# T-Board-328_PCB_-_v0_3.net
KiCad netlist of a schematic drawn in EAGLE
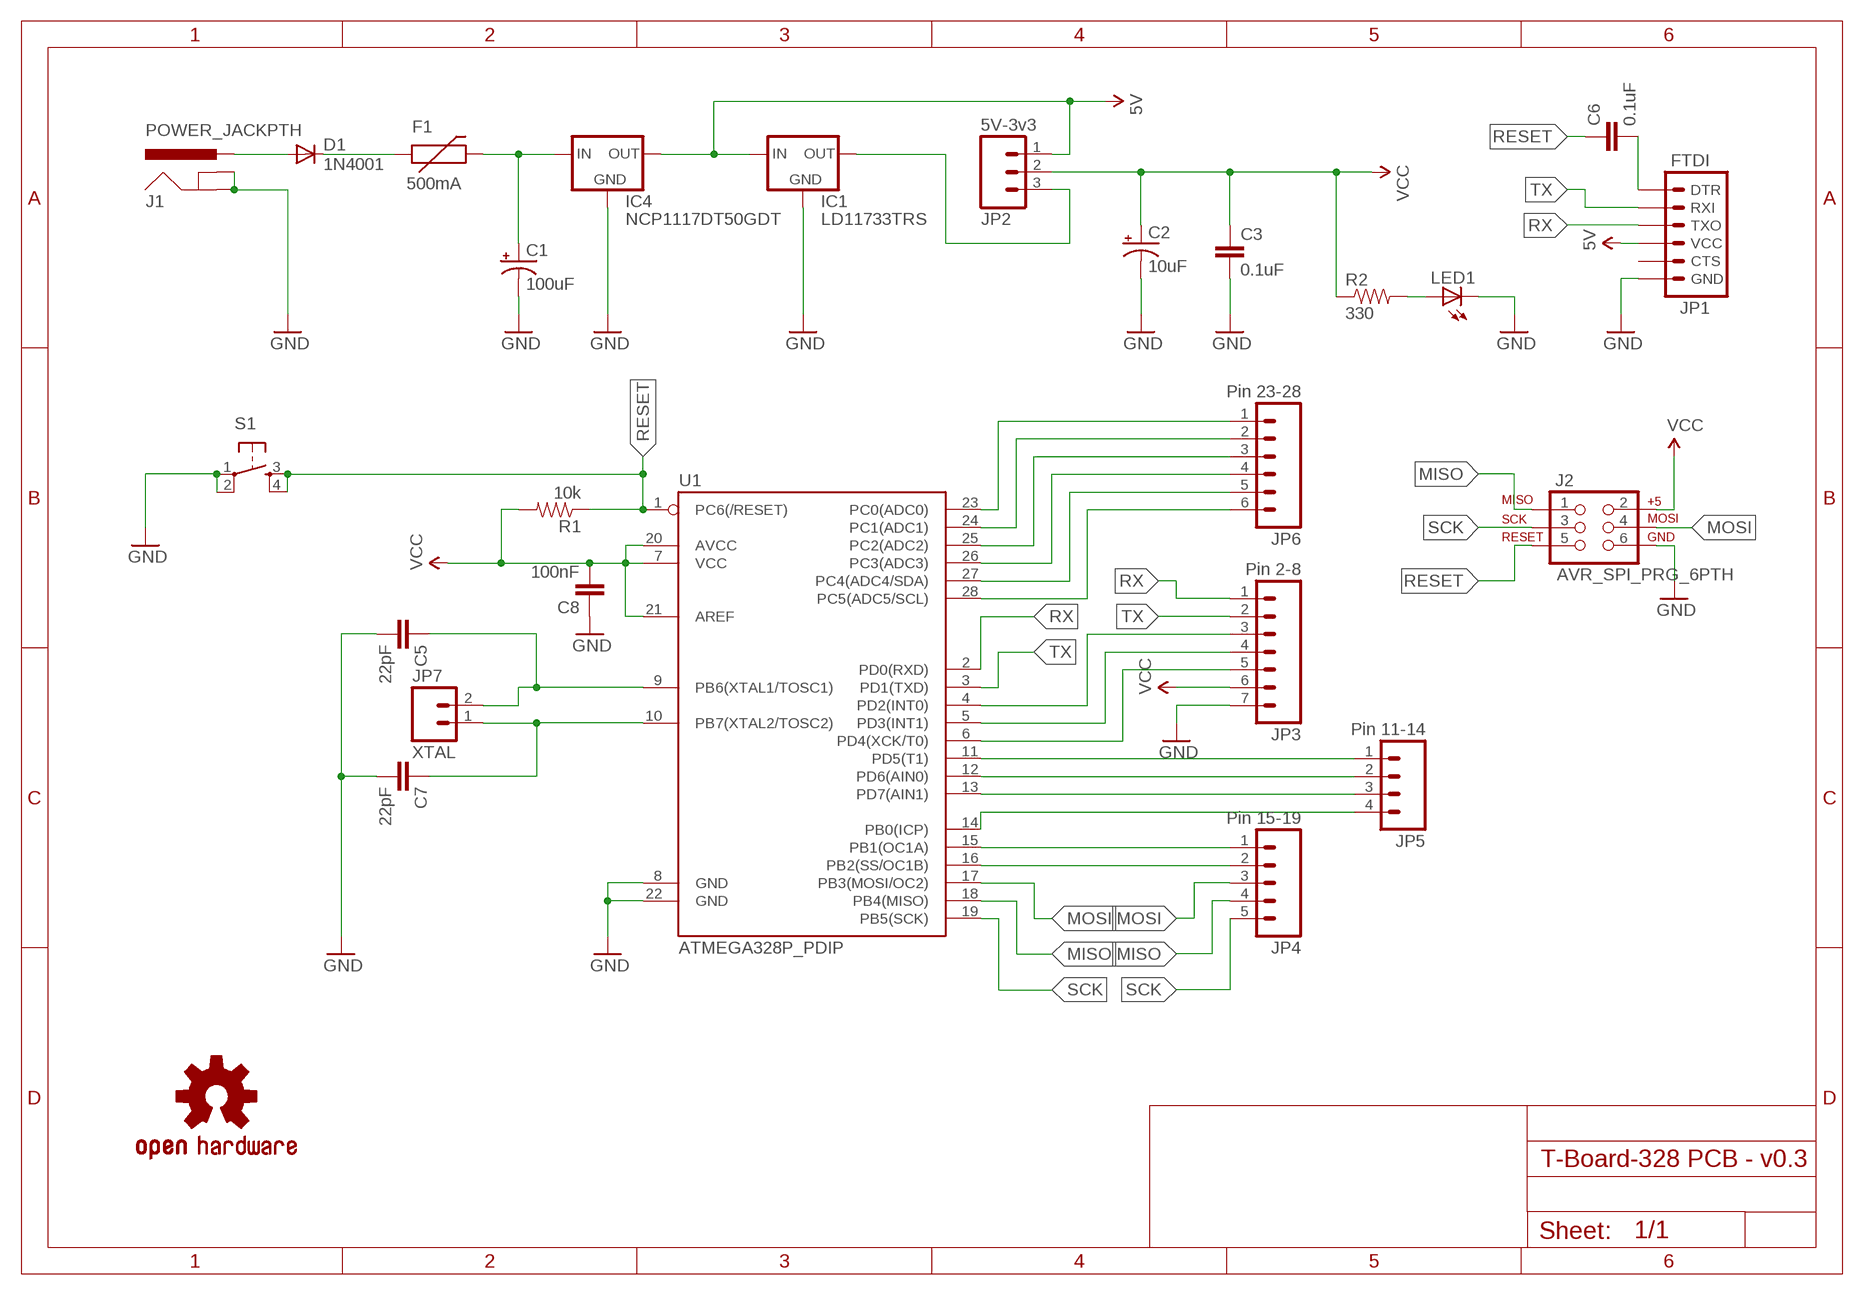
[diagram p0: schematic, sheet 1]

(export (version "E")
  (design (tool "Eeschema 10.0.6"))
  (components
    (comp (ref "C1")
      (value "100uF")
      (footprint "eagle-import:CPOL-RADIAL-100UF-25V")
      (libsource (lib "eagle-import") (part "CAP_POLPTH1"))
    )
    (comp (ref "C2")
      (value "10uF")
      (footprint "eagle-import:CPOL-RADIAL-10UF-25V")
      (libsource (lib "eagle-import") (part "CAP_POLPTH2"))
    )
    (comp (ref "C3")
      (value "0.1uF")
      (footprint "eagle-import:1206")
      (libsource (lib "eagle-import") (part "CAP1206"))
    )
    (comp (ref "C5")
      (value "22pF")
      (footprint "eagle-import:1206")
      (libsource (lib "eagle-import") (part "CAP1206"))
    )
    (comp (ref "C6")
      (value "0.1uF")
      (footprint "eagle-import:1206")
      (libsource (lib "eagle-import") (part "CAP1206"))
    )
    (comp (ref "C7")
      (value "22pF")
      (footprint "eagle-import:1206")
      (libsource (lib "eagle-import") (part "CAP1206"))
    )
    (comp (ref "C8")
      (value "100nF")
      (footprint "eagle-import:1206")
      (libsource (lib "eagle-import") (part "CAP1206"))
    )
    (comp (ref "D1")
      (value "1N4001")
      (footprint "eagle-import:DIODE-1N4001")
      (libsource (lib "eagle-import") (part "DIODEPTH"))
    )
    (comp (ref "F1")
      (value "500mA")
      (footprint "eagle-import:PTC")
      (libsource (lib "eagle-import") (part "PTCPTH"))
    )
    (comp (ref "IC1")
      (value "LD11733TRS")
      (footprint "eagle-import:SOT223")
      (libsource (lib "eagle-import") (part "LD117S33TR"))
    )
    (comp (ref "IC4")
      (value "NCP1117DT50GDT")
      (footprint "eagle-import:DPACK")
      (libsource (lib "eagle-import") (part "NCP1117DTDT50G"))
    )
    (comp (ref "J1")
      (value "POWER_JACKPTH")
      (footprint "eagle-import:POWER_JACK_PTH")
      (libsource (lib "eagle-import") (part "POWER_JACKPTH"))
    )
    (comp (ref "J2")
      (value "AVR_SPI_PRG_6PTH")
      (footprint "eagle-import:2X3")
      (libsource (lib "eagle-import") (part "AVR_SPI_PRG_6PTH"))
    )
    (comp (ref "JP1")
      (value "FTDI")
      (footprint "eagle-import:1X06_LONGPADS")
      (libsource (lib "eagle-import") (part "ARDUINO_SERIAL_PROGRAMLONGPADS"))
    )
    (comp (ref "JP2")
      (value "5V-3v3")
      (footprint "eagle-import:1X03")
      (libsource (lib "eagle-import") (part "M03PTH"))
    )
    (comp (ref "JP3")
      (value "Pin 2-8")
      (footprint "eagle-import:1X07")
      (libsource (lib "eagle-import") (part "M07"))
    )
    (comp (ref "JP4")
      (value "Pin 15-19")
      (footprint "eagle-import:1X05")
      (libsource (lib "eagle-import") (part "M05PTH"))
    )
    (comp (ref "JP5")
      (value "Pin 11-14")
      (footprint "eagle-import:1X04")
      (libsource (lib "eagle-import") (part "M04-NON-POLARPTH"))
    )
    (comp (ref "JP6")
      (value "Pin 23-28")
      (footprint "eagle-import:1X06")
      (libsource (lib "eagle-import") (part "M06SIP"))
    )
    (comp (ref "JP7")
      (value "XTAL")
      (footprint "eagle-import:1X02")
      (libsource (lib "eagle-import") (part "M02PTH"))
    )
    (comp (ref "LED1")
      (value "LED1206")
      (footprint "eagle-import:LED-1206")
      (libsource (lib "eagle-import") (part "LED1206"))
    )
    (comp (ref "LOGO1")
      (value "OSHW-LOGOS")
      (footprint "eagle-import:OSHW-LOGO-S")
      (libsource (lib "eagle-import") (part "OSHW-LOGOS"))
    )
    (comp (ref "R1")
      (value "10k")
      (footprint "eagle-import:1206")
      (libsource (lib "eagle-import") (part "RESISTOR1206"))
    )
    (comp (ref "R2")
      (value "330")
      (footprint "eagle-import:1206")
      (libsource (lib "eagle-import") (part "RESISTOR1206"))
    )
    (comp (ref "S1")
      (value "TAC_SWITCHPTH")
      (footprint "eagle-import:TACTILE-PTH")
      (libsource (lib "eagle-import") (part "TAC_SWITCHPTH"))
    )
    (comp (ref "U1")
      (value "ATMEGA328P_PDIP")
      (footprint "eagle-import:DIL28-3")
      (libsource (lib "eagle-import") (part "ATMEGA328P_PDIP"))
    )
  )
  (nets
    (net (code "1") (name "5V") (class "Default")
      (node (ref "IC1") (pin "3") (pinfunction "IN_3") (pintype "input"))
      (node (ref "IC4") (pin "4") (pinfunction "OUT_4") (pintype "passive"))
      (node (ref "JP1") (pin "4") (pinfunction "VCC_4") (pintype "passive"))
      (node (ref "JP2") (pin "1") (pinfunction "1_1") (pintype "passive"))
    )
    (net (code "2") (name "GND") (class "Default")
      (node (ref "C1") (pin "2") (pinfunction "-_2") (pintype "passive"))
      (node (ref "C2") (pin "2") (pinfunction "-_2") (pintype "passive"))
      (node (ref "C3") (pin "2") (pinfunction "2_2") (pintype "passive"))
      (node (ref "C5") (pin "2") (pinfunction "2_2") (pintype "passive"))
      (node (ref "C7") (pin "2") (pinfunction "2_2") (pintype "passive"))
      (node (ref "C8") (pin "1") (pinfunction "1_1") (pintype "passive"))
      (node (ref "IC1") (pin "1") (pinfunction "GND_1") (pintype "input"))
      (node (ref "IC4") (pin "1") (pinfunction "GND_1") (pintype "input"))
      (node (ref "J1") (pin "GND") (pinfunction "GND_GND") (pintype "bidirectional"))
      (node (ref "J1") (pin "GNDBREAK") (pinfunction "GNDBREAK_GNDBREAK") (pintype "bidirectional"))
      (node (ref "J2") (pin "6") (pinfunction "6_6") (pintype "passive"))
      (node (ref "JP1") (pin "6") (pinfunction "GND_6") (pintype "passive"))
      (node (ref "JP3") (pin "7") (pinfunction "7_7") (pintype "passive"))
      (node (ref "LED1") (pin "C") (pinfunction "C_C") (pintype "passive"))
      (node (ref "S1") (pin "1") (pinfunction "1_1") (pintype "passive"))
      (node (ref "S1") (pin "2") (pinfunction "2_2") (pintype "passive"))
      (node (ref "U1") (pin "22") (pinfunction "GND_22") (pintype "bidirectional"))
      (node (ref "U1") (pin "8") (pinfunction "GND_8") (pintype "bidirectional"))
    )
    (net (code "3") (name "MISO") (class "Default")
      (node (ref "J2") (pin "1") (pinfunction "1_1") (pintype "passive"))
      (node (ref "JP4") (pin "4") (pinfunction "4_4") (pintype "passive"))
      (node (ref "U1") (pin "18") (pinfunction "PB4(MISO)_18") (pintype "bidirectional"))
    )
    (net (code "4") (name "MOSI") (class "Default")
      (node (ref "J2") (pin "4") (pinfunction "4_4") (pintype "passive"))
      (node (ref "JP4") (pin "3") (pinfunction "3_3") (pintype "passive"))
      (node (ref "U1") (pin "17") (pinfunction "PB3(MOSI/OC2)_17") (pintype "bidirectional"))
    )
    (net (code "5") (name "Net-(C1-+)") (class "Default")
      (node (ref "C1") (pin "1") (pinfunction "+_1") (pintype "passive"))
      (node (ref "F1") (pin "P$2") (pinfunction "2_P$2") (pintype "bidirectional"))
      (node (ref "IC4") (pin "3") (pinfunction "IN_3") (pintype "input"))
    )
    (net (code "6") (name "Net-(D1-PadA)") (class "Default")
      (node (ref "D1") (pin "A") (pinfunction "A_A") (pintype "passive"))
      (node (ref "J1") (pin "PWR") (pinfunction "PWR_PWR") (pintype "bidirectional"))
    )
    (net (code "7") (name "Net-(F1-1)") (class "Default")
      (node (ref "D1") (pin "C") (pinfunction "C_C") (pintype "passive"))
      (node (ref "F1") (pin "P$1") (pinfunction "1_P$1") (pintype "bidirectional"))
    )
    (net (code "8") (name "Net-(IC1-OUT)") (class "Default")
      (node (ref "IC1") (pin "4") (pinfunction "OUT_4") (pintype "passive"))
      (node (ref "JP2") (pin "3") (pinfunction "3_3") (pintype "passive"))
    )
    (net (code "9") (name "Net-(JP1-DTR)") (class "Default")
      (node (ref "C6") (pin "2") (pinfunction "2_2") (pintype "passive"))
      (node (ref "JP1") (pin "1") (pinfunction "DTR_1") (pintype "passive"))
    )
    (net (code "10") (name "Net-(LED1-PadA)") (class "Default")
      (node (ref "LED1") (pin "A") (pinfunction "A_A") (pintype "passive"))
      (node (ref "R2") (pin "2") (pinfunction "2_2") (pintype "passive"))
    )
    (net (code "11") (name "Net-(U1-PB0(ICP))") (class "Default")
      (node (ref "JP5") (pin "4") (pinfunction "4_4") (pintype "passive"))
      (node (ref "U1") (pin "14") (pinfunction "PB0(ICP)_14") (pintype "bidirectional"))
    )
    (net (code "12") (name "Net-(U1-PB1(OC1A))") (class "Default")
      (node (ref "JP4") (pin "1") (pinfunction "1_1") (pintype "passive"))
      (node (ref "U1") (pin "15") (pinfunction "PB1(OC1A)_15") (pintype "bidirectional"))
    )
    (net (code "13") (name "Net-(U1-PB2(SS{slash}OC1B))") (class "Default")
      (node (ref "JP4") (pin "2") (pinfunction "2_2") (pintype "passive"))
      (node (ref "U1") (pin "16") (pinfunction "PB2(SS/OC1B)_16") (pintype "bidirectional"))
    )
    (net (code "14") (name "Net-(U1-PB6(XTAL1{slash}TOSC1))") (class "Default")
      (node (ref "C5") (pin "1") (pinfunction "1_1") (pintype "passive"))
      (node (ref "JP7") (pin "2") (pinfunction "2_2") (pintype "passive"))
      (node (ref "U1") (pin "9") (pinfunction "PB6(XTAL1/TOSC1)_9") (pintype "bidirectional"))
    )
    (net (code "15") (name "Net-(U1-PB7(XTAL2{slash}TOSC2))") (class "Default")
      (node (ref "C7") (pin "1") (pinfunction "1_1") (pintype "passive"))
      (node (ref "JP7") (pin "1") (pinfunction "1_1") (pintype "passive"))
      (node (ref "U1") (pin "10") (pinfunction "PB7(XTAL2/TOSC2)_10") (pintype "bidirectional"))
    )
    (net (code "16") (name "Net-(U1-PC0(ADC0))") (class "Default")
      (node (ref "JP6") (pin "1") (pinfunction "1_1") (pintype "passive"))
      (node (ref "U1") (pin "23") (pinfunction "PC0(ADC0)_23") (pintype "bidirectional"))
    )
    (net (code "17") (name "Net-(U1-PC1(ADC1))") (class "Default")
      (node (ref "JP6") (pin "2") (pinfunction "2_2") (pintype "passive"))
      (node (ref "U1") (pin "24") (pinfunction "PC1(ADC1)_24") (pintype "bidirectional"))
    )
    (net (code "18") (name "Net-(U1-PC2(ADC2))") (class "Default")
      (node (ref "JP6") (pin "3") (pinfunction "3_3") (pintype "passive"))
      (node (ref "U1") (pin "25") (pinfunction "PC2(ADC2)_25") (pintype "bidirectional"))
    )
    (net (code "19") (name "Net-(U1-PC3(ADC3))") (class "Default")
      (node (ref "JP6") (pin "4") (pinfunction "4_4") (pintype "passive"))
      (node (ref "U1") (pin "26") (pinfunction "PC3(ADC3)_26") (pintype "bidirectional"))
    )
    (net (code "20") (name "Net-(U1-PC4(ADC4{slash}SDA))") (class "Default")
      (node (ref "JP6") (pin "5") (pinfunction "5_5") (pintype "passive"))
      (node (ref "U1") (pin "27") (pinfunction "PC4(ADC4/SDA)_27") (pintype "bidirectional"))
    )
    (net (code "21") (name "Net-(U1-PC5(ADC5{slash}SCL))") (class "Default")
      (node (ref "JP6") (pin "6") (pinfunction "6_6") (pintype "passive"))
      (node (ref "U1") (pin "28") (pinfunction "PC5(ADC5/SCL)_28") (pintype "bidirectional"))
    )
    (net (code "22") (name "Net-(U1-PD2(INT0))") (class "Default")
      (node (ref "JP3") (pin "3") (pinfunction "3_3") (pintype "passive"))
      (node (ref "U1") (pin "4") (pinfunction "PD2(INT0)_4") (pintype "bidirectional"))
    )
    (net (code "23") (name "Net-(U1-PD3(INT1))") (class "Default")
      (node (ref "JP3") (pin "4") (pinfunction "4_4") (pintype "passive"))
      (node (ref "U1") (pin "5") (pinfunction "PD3(INT1)_5") (pintype "bidirectional"))
    )
    (net (code "24") (name "Net-(U1-PD4(XCK{slash}T0))") (class "Default")
      (node (ref "JP3") (pin "5") (pinfunction "5_5") (pintype "passive"))
      (node (ref "U1") (pin "6") (pinfunction "PD4(XCK/T0)_6") (pintype "bidirectional"))
    )
    (net (code "25") (name "Net-(U1-PD5(T1))") (class "Default")
      (node (ref "JP5") (pin "1") (pinfunction "1_1") (pintype "passive"))
      (node (ref "U1") (pin "11") (pinfunction "PD5(T1)_11") (pintype "bidirectional"))
    )
    (net (code "26") (name "Net-(U1-PD6(AIN0))") (class "Default")
      (node (ref "JP5") (pin "2") (pinfunction "2_2") (pintype "passive"))
      (node (ref "U1") (pin "12") (pinfunction "PD6(AIN0)_12") (pintype "bidirectional"))
    )
    (net (code "27") (name "Net-(U1-PD7(AIN1))") (class "Default")
      (node (ref "JP5") (pin "3") (pinfunction "3_3") (pintype "passive"))
      (node (ref "U1") (pin "13") (pinfunction "PD7(AIN1)_13") (pintype "bidirectional"))
    )
    (net (code "28") (name "RESET") (class "Default")
      (node (ref "C6") (pin "1") (pinfunction "1_1") (pintype "passive"))
      (node (ref "J2") (pin "5") (pinfunction "5_5") (pintype "passive"))
      (node (ref "R1") (pin "1") (pinfunction "1_1") (pintype "passive"))
      (node (ref "S1") (pin "3") (pinfunction "3_3") (pintype "passive"))
      (node (ref "S1") (pin "4") (pinfunction "4_4") (pintype "passive"))
      (node (ref "U1") (pin "1") (pinfunction "PC6(/RESET)_1") (pintype "bidirectional"))
    )
    (net (code "29") (name "RX") (class "Default")
      (node (ref "JP1") (pin "3") (pinfunction "TXO_3") (pintype "passive"))
      (node (ref "JP3") (pin "1") (pinfunction "1_1") (pintype "passive"))
      (node (ref "U1") (pin "2") (pinfunction "PD0(RXD)_2") (pintype "bidirectional"))
    )
    (net (code "30") (name "SCK") (class "Default")
      (node (ref "J2") (pin "3") (pinfunction "3_3") (pintype "passive"))
      (node (ref "JP4") (pin "5") (pinfunction "5_5") (pintype "passive"))
      (node (ref "U1") (pin "19") (pinfunction "PB5(SCK)_19") (pintype "bidirectional"))
    )
    (net (code "31") (name "TX") (class "Default")
      (node (ref "JP1") (pin "2") (pinfunction "RXI_2") (pintype "passive"))
      (node (ref "JP3") (pin "2") (pinfunction "2_2") (pintype "passive"))
      (node (ref "U1") (pin "3") (pinfunction "PD1(TXD)_3") (pintype "bidirectional"))
    )
    (net (code "32") (name "VCC") (class "Default")
      (node (ref "C2") (pin "1") (pinfunction "+_1") (pintype "passive"))
      (node (ref "C3") (pin "1") (pinfunction "1_1") (pintype "passive"))
      (node (ref "C8") (pin "2") (pinfunction "2_2") (pintype "passive"))
      (node (ref "J2") (pin "2") (pinfunction "2_2") (pintype "passive"))
      (node (ref "JP2") (pin "2") (pinfunction "2_2") (pintype "passive"))
      (node (ref "JP3") (pin "6") (pinfunction "6_6") (pintype "passive"))
      (node (ref "R1") (pin "2") (pinfunction "2_2") (pintype "passive"))
      (node (ref "R2") (pin "1") (pinfunction "1_1") (pintype "passive"))
      (node (ref "U1") (pin "20") (pinfunction "AVCC_20") (pintype "bidirectional"))
      (node (ref "U1") (pin "21") (pinfunction "AREF_21") (pintype "bidirectional"))
      (node (ref "U1") (pin "7") (pinfunction "VCC_7") (pintype "bidirectional"))
    )
    (net (code "33") (name "unconnected-(JP1-CTS-Pad5)") (class "Default")
      (node (ref "JP1") (pin "5") (pinfunction "CTS_5") (pintype "passive"))
    )
  )
)
